# SNES_SCIC_IGR_D4.net
KiCad netlist of a schematic drawn in EAGLE
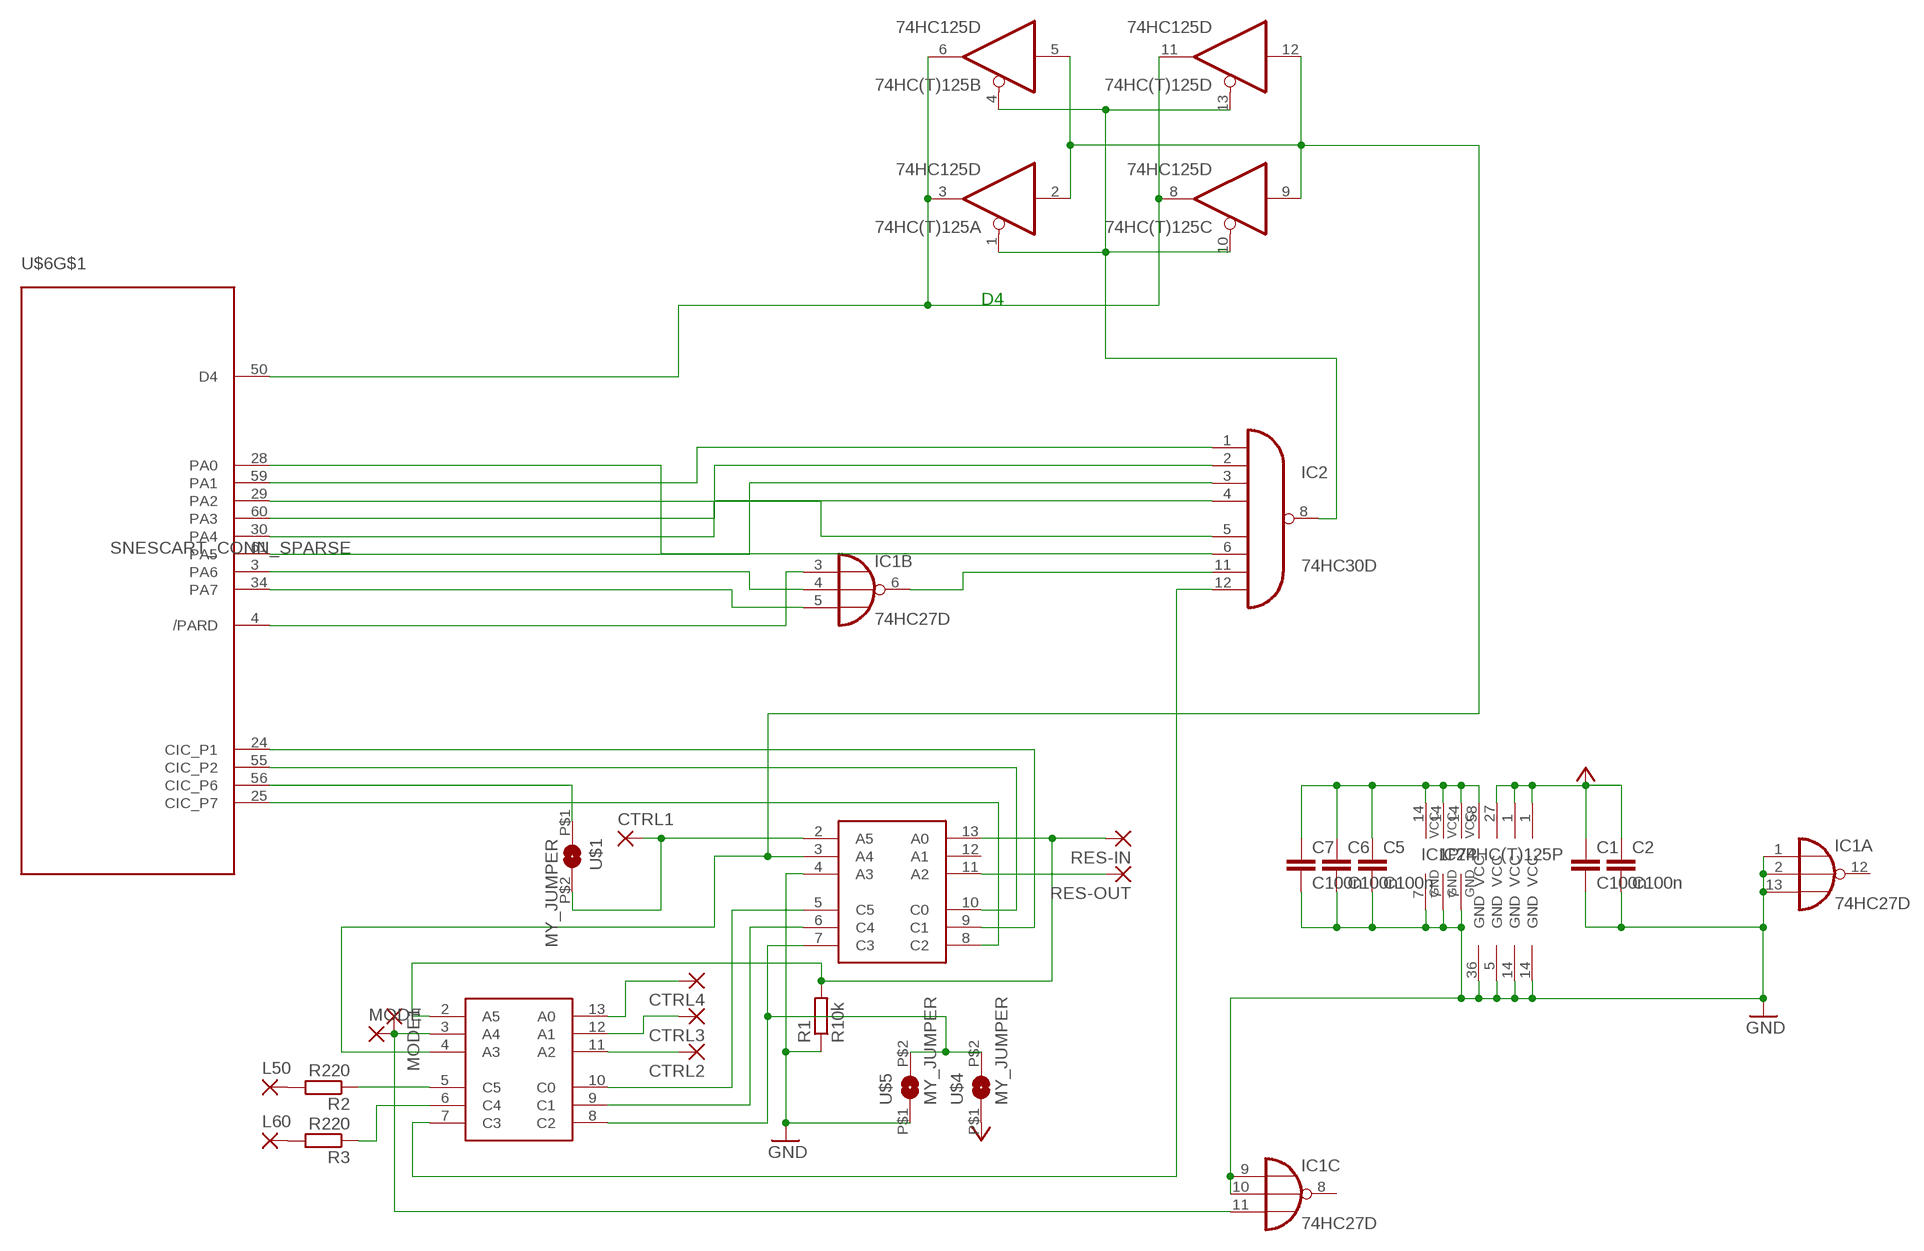
[diagram p0: schematic, sheet 1]

(export (version "E")
  (design (tool "Eeschema 10.0.6"))
  (components
    (comp (ref "74HC(T)125")
      (value "74HC125D")
      (footprint "eagle-import:SO14")
      (libsource (lib "eagle-import") (part "74125DHC"))
    )
    (comp (ref "C1")
      (value "C100n")
      (footprint "eagle-import:Z0805")
      (libsource (lib "eagle-import") (part "C0805"))
    )
    (comp (ref "C2")
      (value "C100n")
      (footprint "eagle-import:Z0805")
      (libsource (lib "eagle-import") (part "C0805"))
    )
    (comp (ref "C5")
      (value "C100n")
      (footprint "eagle-import:Z0805")
      (libsource (lib "eagle-import") (part "C0805"))
    )
    (comp (ref "C6")
      (value "C100n")
      (footprint "eagle-import:Z0805")
      (libsource (lib "eagle-import") (part "C0805"))
    )
    (comp (ref "C7")
      (value "C100n")
      (footprint "eagle-import:Z0805")
      (libsource (lib "eagle-import") (part "C0805"))
    )
    (comp (ref "CTRL1")
      (value "SMD2")
      (footprint "eagle-import:SMD1,27-2,54")
      (libsource (lib "eagle-import") (part "SMD2"))
    )
    (comp (ref "CTRL2")
      (value "SMD2")
      (footprint "eagle-import:SMD1,27-2,54")
      (libsource (lib "eagle-import") (part "SMD2"))
    )
    (comp (ref "CTRL3")
      (value "SMD2")
      (footprint "eagle-import:SMD1,27-2,54")
      (libsource (lib "eagle-import") (part "SMD2"))
    )
    (comp (ref "CTRL4")
      (value "SMD2")
      (footprint "eagle-import:SMD1,27-2,54")
      (libsource (lib "eagle-import") (part "SMD2"))
    )
    (comp (ref "IC1")
      (value "74HC27D")
      (footprint "eagle-import:SO14")
      (libsource (lib "eagle-import") (part "7427DHC"))
    )
    (comp (ref "IC2")
      (value "74HC30D")
      (footprint "eagle-import:SO14")
      (libsource (lib "eagle-import") (part "7430DHC"))
    )
    (comp (ref "L50")
      (value "SMD2")
      (footprint "eagle-import:SMD1,27-2,54")
      (libsource (lib "eagle-import") (part "SMD2"))
    )
    (comp (ref "L60")
      (value "SMD2")
      (footprint "eagle-import:SMD1,27-2,54")
      (libsource (lib "eagle-import") (part "SMD2"))
    )
    (comp (ref "MODE")
      (value "SMD2")
      (footprint "eagle-import:SMD1,27-2,54")
      (libsource (lib "eagle-import") (part "SMD2"))
    )
    (comp (ref "MODE1")
      (value "SMD2")
      (footprint "eagle-import:SMD1,27-2,54")
      (libsource (lib "eagle-import") (part "SMD2"))
    )
    (comp (ref "R1")
      (value "R10k")
      (footprint "eagle-import:Z0805")
      (libsource (lib "eagle-import") (part "R0805"))
    )
    (comp (ref "R2")
      (value "R220")
      (footprint "eagle-import:Z0805")
      (libsource (lib "eagle-import") (part "R0805"))
    )
    (comp (ref "R3")
      (value "R220")
      (footprint "eagle-import:Z0805")
      (libsource (lib "eagle-import") (part "R0805"))
    )
    (comp (ref "RES-IN")
      (value "SMD2")
      (footprint "eagle-import:SMD1,27-2,54")
      (libsource (lib "eagle-import") (part "SMD2"))
    )
    (comp (ref "RES-OUT")
      (value "SMD2")
      (footprint "eagle-import:SMD1,27-2,54")
      (libsource (lib "eagle-import") (part "SMD2"))
    )
    (comp (ref "U$1")
      (value "MY_JUMPER")
      (footprint "eagle-import:MYJUMP")
      (libsource (lib "eagle-import") (part "MY_JUMPER"))
    )
    (comp (ref "U$2")
      (value "PIC16F630_SIMPLE")
      (footprint "eagle-import:PIC16F630")
      (libsource (lib "eagle-import") (part "PIC16F630_SIMPLE"))
    )
    (comp (ref "U$3")
      (value "PIC16F630_SIMPLE")
      (footprint "eagle-import:PIC16F630")
      (libsource (lib "eagle-import") (part "PIC16F630_SIMPLE"))
    )
    (comp (ref "U$4")
      (value "MY_JUMPER")
      (footprint "eagle-import:MYJUMP")
      (libsource (lib "eagle-import") (part "MY_JUMPER"))
    )
    (comp (ref "U$5")
      (value "MY_JUMPER")
      (footprint "eagle-import:MYJUMP")
      (libsource (lib "eagle-import") (part "MY_JUMPER"))
    )
    (comp (ref "U$6")
      (value "SNESCART_CONN_SPARSE")
      (footprint "eagle-import:SNESCART_CONN_SPARSE")
      (libsource (lib "eagle-import") (part "SNESCART_CONN_SPARSE"))
    )
  )
  (nets
    (net (code "1") (name "+5V") (class "Default")
      (node (ref "C1") (pin "1") (pinfunction "1_1") (pintype "passive"))
      (node (ref "C2") (pin "1") (pinfunction "1_1") (pintype "passive"))
      (node (ref "U$2") (pin "1") (pinfunction "VCC_1") (pintype "bidirectional"))
      (node (ref "U$3") (pin "1") (pinfunction "VCC_1") (pintype "bidirectional"))
      (node (ref "U$4") (pin "P$1") (pinfunction "1_P$1") (pintype "passive"))
      (node (ref "U$6") (pin "27") (pinfunction "VCC_27") (pintype "bidirectional"))
    )
    (net (code "2") (name "GND") (class "Default")
      (node (ref "74HC(T)125") (pin "7") (pinfunction "GND_7") (pintype "power_in"))
      (node (ref "C1") (pin "2") (pinfunction "2_2") (pintype "passive"))
      (node (ref "C2") (pin "2") (pinfunction "2_2") (pintype "passive"))
      (node (ref "C5") (pin "2") (pinfunction "2_2") (pintype "passive"))
      (node (ref "C6") (pin "2") (pinfunction "2_2") (pintype "passive"))
      (node (ref "C7") (pin "2") (pinfunction "2_2") (pintype "passive"))
      (node (ref "IC1") (pin "1") (pinfunction "I0_1") (pintype "input"))
      (node (ref "IC1") (pin "10") (pinfunction "I1_10") (pintype "input"))
      (node (ref "IC1") (pin "13") (pinfunction "I2_13") (pintype "input"))
      (node (ref "IC1") (pin "2") (pinfunction "I1_2") (pintype "input"))
      (node (ref "IC1") (pin "7") (pinfunction "GND_7") (pintype "power_in"))
      (node (ref "IC1") (pin "9") (pinfunction "I0_9") (pintype "input"))
      (node (ref "IC2") (pin "7") (pinfunction "GND_7") (pintype "power_in"))
      (node (ref "R1") (pin "1") (pinfunction "1_1") (pintype "passive"))
      (node (ref "U$2") (pin "14") (pinfunction "GND_14") (pintype "bidirectional"))
      (node (ref "U$2") (pin "4") (pinfunction "A3_4") (pintype "bidirectional"))
      (node (ref "U$3") (pin "14") (pinfunction "GND_14") (pintype "bidirectional"))
      (node (ref "U$5") (pin "P$1") (pinfunction "1_P$1") (pintype "passive"))
      (node (ref "U$6") (pin "36") (pinfunction "GND_36") (pintype "bidirectional"))
      (node (ref "U$6") (pin "5") (pinfunction "GND_5") (pintype "bidirectional"))
    )
    (net (code "3") (name "Net-(74HC(T)125A-I)") (class "Default")
      (node (ref "74HC(T)125") (pin "12") (pinfunction "I_12") (pintype "input"))
      (node (ref "74HC(T)125") (pin "2") (pinfunction "I_2") (pintype "input"))
      (node (ref "74HC(T)125") (pin "5") (pinfunction "I_5") (pintype "input"))
      (node (ref "74HC(T)125") (pin "9") (pinfunction "I_9") (pintype "input"))
      (node (ref "U$2") (pin "3") (pinfunction "A4_3") (pintype "bidirectional"))
      (node (ref "U$3") (pin "4") (pinfunction "A3_4") (pintype "bidirectional"))
    )
    (net (code "4") (name "Net-(74HC(T)125A-O)") (class "Default")
      (node (ref "74HC(T)125") (pin "11") (pinfunction "O_11") (pintype "tri_state"))
      (node (ref "74HC(T)125") (pin "3") (pinfunction "O_3") (pintype "tri_state"))
      (node (ref "74HC(T)125") (pin "6") (pinfunction "O_6") (pintype "tri_state"))
      (node (ref "74HC(T)125") (pin "8") (pinfunction "O_8") (pintype "tri_state"))
      (node (ref "U$6") (pin "50") (pinfunction "D4_50") (pintype "bidirectional"))
    )
    (net (code "5") (name "Net-(74HC(T)125A-OE)") (class "Default")
      (node (ref "74HC(T)125") (pin "1") (pinfunction "OE_1") (pintype "input"))
      (node (ref "74HC(T)125") (pin "10") (pinfunction "OE_10") (pintype "input"))
      (node (ref "74HC(T)125") (pin "13") (pinfunction "OE_13") (pintype "input"))
      (node (ref "74HC(T)125") (pin "4") (pinfunction "OE_4") (pintype "input"))
      (node (ref "IC2") (pin "8") (pinfunction "O_8") (pintype "output"))
    )
    (net (code "6") (name "Net-(74HC(T)125E-VCC)") (class "Default")
      (node (ref "74HC(T)125") (pin "14") (pinfunction "VCC_14") (pintype "power_in"))
      (node (ref "C5") (pin "1") (pinfunction "1_1") (pintype "passive"))
      (node (ref "C6") (pin "1") (pinfunction "1_1") (pintype "passive"))
      (node (ref "C7") (pin "1") (pinfunction "1_1") (pintype "passive"))
      (node (ref "IC1") (pin "14") (pinfunction "VCC_14") (pintype "power_in"))
      (node (ref "IC2") (pin "14") (pinfunction "VCC_14") (pintype "power_in"))
      (node (ref "U$6") (pin "58") (pinfunction "VCC_58") (pintype "bidirectional"))
    )
    (net (code "7") (name "Net-(CTRL1-P)") (class "Default")
      (node (ref "CTRL1") (pin "1") (pinfunction "P_1") (pintype "passive"))
      (node (ref "U$1") (pin "P$2") (pinfunction "2_P$2") (pintype "passive"))
      (node (ref "U$2") (pin "2") (pinfunction "A5_2") (pintype "bidirectional"))
    )
    (net (code "8") (name "Net-(CTRL2-P)") (class "Default")
      (node (ref "CTRL2") (pin "1") (pinfunction "P_1") (pintype "passive"))
      (node (ref "U$3") (pin "11") (pinfunction "A2_11") (pintype "bidirectional"))
    )
    (net (code "9") (name "Net-(CTRL3-P)") (class "Default")
      (node (ref "CTRL3") (pin "1") (pinfunction "P_1") (pintype "passive"))
      (node (ref "U$3") (pin "12") (pinfunction "A1_12") (pintype "bidirectional"))
    )
    (net (code "10") (name "Net-(CTRL4-P)") (class "Default")
      (node (ref "CTRL4") (pin "1") (pinfunction "P_1") (pintype "passive"))
      (node (ref "U$3") (pin "13") (pinfunction "A0_13") (pintype "bidirectional"))
    )
    (net (code "11") (name "Net-(IC1B-I0)") (class "Default")
      (node (ref "IC1") (pin "3") (pinfunction "I0_3") (pintype "input"))
      (node (ref "U$6") (pin "4") (pinfunction "/PARD_4") (pintype "bidirectional"))
    )
    (net (code "12") (name "Net-(IC1B-I1)") (class "Default")
      (node (ref "IC1") (pin "4") (pinfunction "I1_4") (pintype "input"))
      (node (ref "U$6") (pin "3") (pinfunction "PA6_3") (pintype "bidirectional"))
    )
    (net (code "13") (name "Net-(IC1B-I2)") (class "Default")
      (node (ref "IC1") (pin "5") (pinfunction "I2_5") (pintype "input"))
      (node (ref "U$6") (pin "34") (pinfunction "PA7_34") (pintype "bidirectional"))
    )
    (net (code "14") (name "Net-(IC1B-O)") (class "Default")
      (node (ref "IC1") (pin "6") (pinfunction "O_6") (pintype "output"))
      (node (ref "IC2") (pin "11") (pinfunction "I6_11") (pintype "input"))
    )
    (net (code "15") (name "Net-(IC1C-I2)") (class "Default")
      (node (ref "IC1") (pin "11") (pinfunction "I2_11") (pintype "input"))
      (node (ref "MODE") (pin "1") (pinfunction "P_1") (pintype "passive"))
      (node (ref "MODE1") (pin "1") (pinfunction "P_1") (pintype "passive"))
      (node (ref "U$3") (pin "3") (pinfunction "A4_3") (pintype "bidirectional"))
    )
    (net (code "16") (name "Net-(IC2A-I0)") (class "Default")
      (node (ref "IC2") (pin "1") (pinfunction "I0_1") (pintype "input"))
      (node (ref "U$6") (pin "59") (pinfunction "PA1_59") (pintype "bidirectional"))
    )
    (net (code "17") (name "Net-(IC2A-I1)") (class "Default")
      (node (ref "IC2") (pin "2") (pinfunction "I1_2") (pintype "input"))
      (node (ref "U$6") (pin "60") (pinfunction "PA3_60") (pintype "bidirectional"))
    )
    (net (code "18") (name "Net-(IC2A-I2)") (class "Default")
      (node (ref "IC2") (pin "3") (pinfunction "I2_3") (pintype "input"))
      (node (ref "U$6") (pin "61") (pinfunction "PA5_61") (pintype "bidirectional"))
    )
    (net (code "19") (name "Net-(IC2A-I3)") (class "Default")
      (node (ref "IC2") (pin "4") (pinfunction "I3_4") (pintype "input"))
      (node (ref "U$6") (pin "30") (pinfunction "PA4_30") (pintype "bidirectional"))
    )
    (net (code "20") (name "Net-(IC2A-I4)") (class "Default")
      (node (ref "IC2") (pin "5") (pinfunction "I4_5") (pintype "input"))
      (node (ref "U$6") (pin "29") (pinfunction "PA2_29") (pintype "bidirectional"))
    )
    (net (code "21") (name "Net-(IC2A-I5)") (class "Default")
      (node (ref "IC2") (pin "6") (pinfunction "I5_6") (pintype "input"))
      (node (ref "U$6") (pin "28") (pinfunction "PA0_28") (pintype "bidirectional"))
    )
    (net (code "22") (name "Net-(IC2A-I7)") (class "Default")
      (node (ref "IC2") (pin "12") (pinfunction "I7_12") (pintype "input"))
      (node (ref "U$3") (pin "7") (pinfunction "C3_7") (pintype "bidirectional"))
    )
    (net (code "23") (name "Net-(L50-P)") (class "Default")
      (node (ref "L50") (pin "1") (pinfunction "P_1") (pintype "passive"))
      (node (ref "R2") (pin "2") (pinfunction "2_2") (pintype "passive"))
    )
    (net (code "24") (name "Net-(L60-P)") (class "Default")
      (node (ref "L60") (pin "1") (pinfunction "P_1") (pintype "passive"))
      (node (ref "R3") (pin "2") (pinfunction "2_2") (pintype "passive"))
    )
    (net (code "25") (name "Net-(RES-IN-P)") (class "Default")
      (node (ref "R1") (pin "2") (pinfunction "2_2") (pintype "passive"))
      (node (ref "RES-IN") (pin "1") (pinfunction "P_1") (pintype "passive"))
      (node (ref "U$2") (pin "13") (pinfunction "A0_13") (pintype "bidirectional"))
      (node (ref "U$3") (pin "2") (pinfunction "A5_2") (pintype "bidirectional"))
    )
    (net (code "26") (name "Net-(RES-OUT-P)") (class "Default")
      (node (ref "RES-OUT") (pin "1") (pinfunction "P_1") (pintype "passive"))
      (node (ref "U$2") (pin "11") (pinfunction "A2_11") (pintype "bidirectional"))
    )
    (net (code "27") (name "Net-(U$1-1)") (class "Default")
      (node (ref "U$1") (pin "P$1") (pinfunction "1_P$1") (pintype "passive"))
      (node (ref "U$6") (pin "56") (pinfunction "CIC_P6_56") (pintype "bidirectional"))
    )
    (net (code "28") (name "Net-(U$2A-C0)") (class "Default")
      (node (ref "U$2") (pin "10") (pinfunction "C0_10") (pintype "bidirectional"))
      (node (ref "U$6") (pin "55") (pinfunction "CIC_P2_55") (pintype "bidirectional"))
    )
    (net (code "29") (name "Net-(U$2A-C1)") (class "Default")
      (node (ref "U$2") (pin "9") (pinfunction "C1_9") (pintype "bidirectional"))
      (node (ref "U$6") (pin "24") (pinfunction "CIC_P1_24") (pintype "bidirectional"))
    )
    (net (code "30") (name "Net-(U$2A-C2)") (class "Default")
      (node (ref "U$2") (pin "8") (pinfunction "C2_8") (pintype "bidirectional"))
      (node (ref "U$6") (pin "25") (pinfunction "CIC_P7_25") (pintype "bidirectional"))
    )
    (net (code "31") (name "Net-(U$2A-C3)") (class "Default")
      (node (ref "U$2") (pin "7") (pinfunction "C3_7") (pintype "bidirectional"))
      (node (ref "U$3") (pin "8") (pinfunction "C2_8") (pintype "bidirectional"))
      (node (ref "U$4") (pin "P$2") (pinfunction "2_P$2") (pintype "passive"))
      (node (ref "U$5") (pin "P$2") (pinfunction "2_P$2") (pintype "passive"))
    )
    (net (code "32") (name "Net-(U$2A-C4)") (class "Default")
      (node (ref "U$2") (pin "6") (pinfunction "C4_6") (pintype "bidirectional"))
      (node (ref "U$3") (pin "9") (pinfunction "C1_9") (pintype "bidirectional"))
    )
    (net (code "33") (name "Net-(U$2A-C5)") (class "Default")
      (node (ref "U$2") (pin "5") (pinfunction "C5_5") (pintype "bidirectional"))
      (node (ref "U$3") (pin "10") (pinfunction "C0_10") (pintype "bidirectional"))
    )
    (net (code "34") (name "Net-(U$3A-C4)") (class "Default")
      (node (ref "R3") (pin "1") (pinfunction "1_1") (pintype "passive"))
      (node (ref "U$3") (pin "6") (pinfunction "C4_6") (pintype "bidirectional"))
    )
    (net (code "35") (name "Net-(U$3A-C5)") (class "Default")
      (node (ref "R2") (pin "1") (pinfunction "1_1") (pintype "passive"))
      (node (ref "U$3") (pin "5") (pinfunction "C5_5") (pintype "bidirectional"))
    )
    (net (code "36") (name "unconnected-(IC1A-O-Pad12)") (class "Default")
      (node (ref "IC1") (pin "12") (pinfunction "O_12") (pintype "output"))
    )
    (net (code "37") (name "unconnected-(IC1C-O-Pad8)") (class "Default")
      (node (ref "IC1") (pin "8") (pinfunction "O_8") (pintype "output"))
    )
    (net (code "38") (name "unconnected-(U$2A-A1-Pad12)") (class "Default")
      (node (ref "U$2") (pin "12") (pinfunction "A1_12") (pintype "bidirectional"))
    )
  )
)
